# SENSOR.net
KiCad netlist of a schematic drawn in Altium Designer
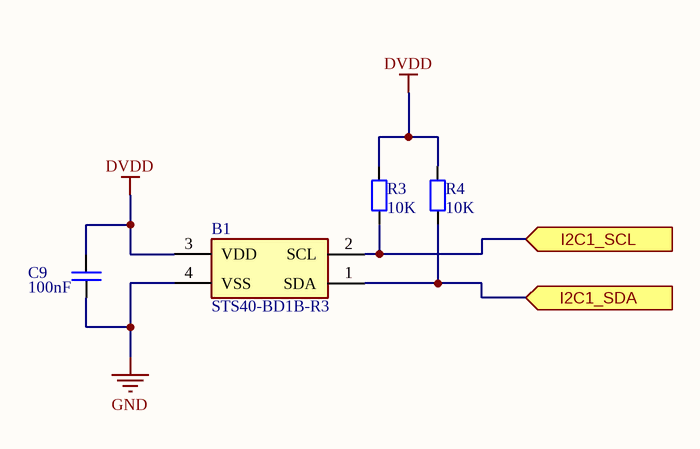
[diagram p0: SENSOR.SchDoc]

(export (version "E")
  (design (tool "Eeschema 10.0.6"))
  (components
    (comp (ref "B1")
      (value "STS40-BD1B-R3")
      (footprint "STS40BD1BR3")
      (description "Board Mount Temperature Sensors Base Accuracy Version, I2C Address 0x45")
      (fields (field (name "MANUFACTURER") "Sensirion"))
      (libsource (lib "STS40-BD1B-R3") (part "STS40-BD1B-R3"))
    )
    (comp (ref "C9")
      (value "100nF")
      (footprint "CAP_SM0805_YAGEOCC2_N")
      (description "CAP 100nF SM0805 X7R 25V YAGEO CC2")
      (fields
        (field (name "MANUFACTURER") "Yageo")
        (field (name "MANUFACTURER PART NUMBER") "CC0805KRX7R8BB104")
      )
      (libsource (lib "Yageo") (part "CC0805KRX7R8BB104"))
    )
    (comp (ref "R3")
      (value "10K")
      (footprint "RES_SM0805_YAGEORC_N")
      (description "RES 10K SM0805 YAGEO RC_L")
      (fields
        (field (name "MANUFACTURER") "Yageo")
        (field (name "MANUFACTURER PART NUMBER") "RC0805FR-0710KL")
      )
      (libsource (lib "Yageo") (part "RC0805FR-0710KL"))
    )
    (comp (ref "R4")
      (value "10K")
      (footprint "RES_SM0805_YAGEORC_N")
      (description "RES 10K SM0805 YAGEO RC_L")
      (fields
        (field (name "MANUFACTURER") "Yageo")
        (field (name "MANUFACTURER PART NUMBER") "RC0805FR-0710KL")
      )
      (libsource (lib "Yageo") (part "RC0805FR-0710KL"))
    )
  )
  (nets
    (net (code "1") (name "/I2C1_SCL") (class "Default")
      (node (ref "B1") (pin "2") (pinfunction "SCL_2") (pintype "passive"))
      (node (ref "R3") (pin "1") (pintype "passive"))
    )
    (net (code "2") (name "/I2C1_SDA") (class "Default")
      (node (ref "B1") (pin "1") (pinfunction "SDA_1") (pintype "passive"))
      (node (ref "R4") (pin "1") (pintype "passive"))
    )
    (net (code "3") (name "DVDD") (class "Default")
      (node (ref "B1") (pin "3") (pinfunction "VDD_3") (pintype "passive"))
      (node (ref "C9") (pin "2") (pintype "passive"))
      (node (ref "R3") (pin "2") (pintype "passive"))
      (node (ref "R4") (pin "2") (pintype "passive"))
    )
    (net (code "4") (name "GND") (class "Default")
      (node (ref "B1") (pin "4") (pinfunction "VSS_4") (pintype "passive"))
      (node (ref "C9") (pin "1") (pintype "passive"))
    )
  )
)
